# PR9023.net
KiCad netlist of a schematic drawn in EAGLE
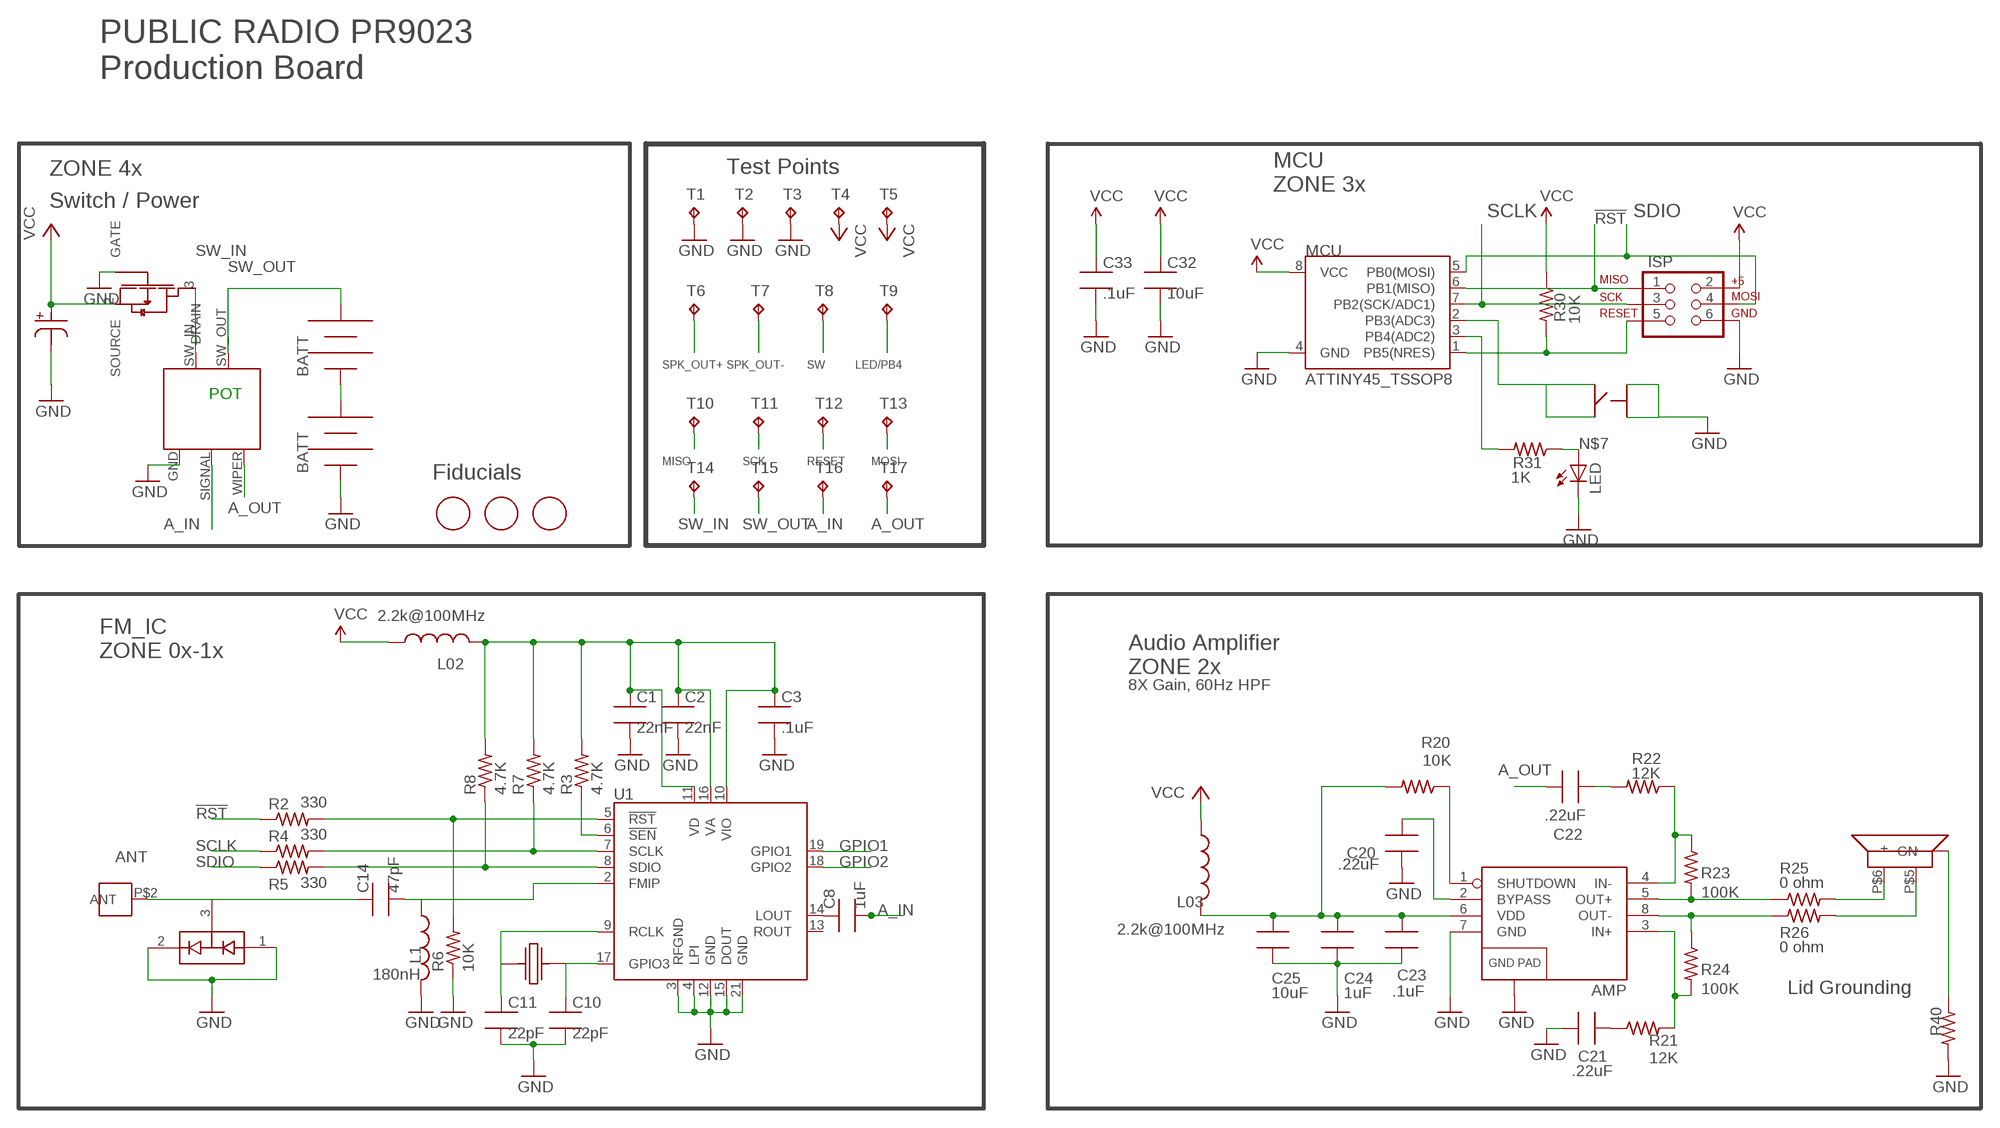
[diagram p0: schematic, sheet 1]

(export (version "E")
  (design (tool "Eeschema 10.0.6"))
  (components
    (comp (ref "AMP")
      (value "TPA6203A1")
      (footprint "eagle-import:8-MSOP")
      (libsource (lib "eagle-import") (part "TPA6203A1"))
    )
    (comp (ref "ANT_MOUNT")
      (value "DNP")
      (footprint "eagle-import:PEM_M3")
      (libsource (lib "eagle-import") (part "M3_PEMNUT"))
    )
    (comp (ref "C1")
      (value "22nF")
      (footprint "eagle-import:0603_CPL")
      (fields
        (field (name "MFG_PN") "CL10B223KB8NNNC")
        (field (name "TOL") "10%")
        (field (name "VOLTAGE") "16V")
      )
      (libsource (lib "eagle-import") (part "C_SMT_0603_CPL"))
    )
    (comp (ref "C2")
      (value "22nF")
      (footprint "eagle-import:0603_CPL")
      (fields
        (field (name "MFG_PN") "CL10B223KB8NNNC")
        (field (name "TOL") "10%")
        (field (name "VOLTAGE") "16V")
      )
      (libsource (lib "eagle-import") (part "C_SMT_0603_CPL"))
    )
    (comp (ref "C3")
      (value ".1uF")
      (footprint "eagle-import:0603_CPL")
      (fields
        (field (name "MFG_PN") "CL10B104KB8SFNC")
        (field (name "TOL") "10%")
        (field (name "VOLTAGE") "16V")
      )
      (libsource (lib "eagle-import") (part "C_SMT_0603_CPL"))
    )
    (comp (ref "C8")
      (value "1uF")
      (footprint "eagle-import:0603_CPL")
      (fields
        (field (name "MFG_PN") "CL10B105KP8NNNC")
        (field (name "TOL") "10%")
        (field (name "VOLTAGE") "10V")
      )
      (libsource (lib "eagle-import") (part "C_SMT_0603_CPL"))
    )
    (comp (ref "C10")
      (value "22pF")
      (footprint "eagle-import:0603_CPL")
      (fields
        (field (name "MFG_PN") "C1608C0G1H220J080AA")
        (field (name "TOL") "5%")
        (field (name "VOLTAGE") "50V")
      )
      (libsource (lib "eagle-import") (part "C_SMT_0603_CPL"))
    )
    (comp (ref "C11")
      (value "22pF")
      (footprint "eagle-import:0603_CPL")
      (fields
        (field (name "MFG_PN") "C1608C0G1H220J080AA")
        (field (name "TOL") "5%")
        (field (name "VOLTAGE") "50V")
      )
      (libsource (lib "eagle-import") (part "C_SMT_0603_CPL"))
    )
    (comp (ref "C14")
      (value "47pF")
      (footprint "eagle-import:0603_CPL")
      (fields
        (field (name "MFG_PN") "CL10C470JB8NCNC")
        (field (name "TOL") "5%")
        (field (name "VOLTAGE") "50V")
      )
      (libsource (lib "eagle-import") (part "C_SMT_0603_CPL"))
    )
    (comp (ref "C20")
      (value ".22uF")
      (footprint "eagle-import:0603_CPL")
      (fields
        (field (name "MFG_PN") "C1608X7R1C224K080AC")
        (field (name "TOL") "10%")
        (field (name "VOLTAGE") "16V")
      )
      (libsource (lib "eagle-import") (part "C_SMT_0603_CPL"))
    )
    (comp (ref "C21")
      (value ".22uF")
      (footprint "eagle-import:0603_CPL")
      (fields
        (field (name "MFG_PN") "C1608X7R1C224K080AC")
        (field (name "TOL") "10%")
        (field (name "VOLTAGE") "16V")
      )
      (libsource (lib "eagle-import") (part "C_SMT_0603_CPL"))
    )
    (comp (ref "C22")
      (value ".22uF")
      (footprint "eagle-import:0603_CPL")
      (fields
        (field (name "MFG_PN") "C1608X7R1C224K080AC")
        (field (name "TOL") "10%")
        (field (name "VOLTAGE") "16V")
      )
      (libsource (lib "eagle-import") (part "C_SMT_0603_CPL"))
    )
    (comp (ref "C23")
      (value ".1uF")
      (footprint "eagle-import:0603_CPL")
      (fields
        (field (name "MFG_PN") "CL10B104KB8SFNC")
        (field (name "TOL") "10%")
        (field (name "VOLTAGE") "16V")
      )
      (libsource (lib "eagle-import") (part "C_SMT_0603_CPL"))
    )
    (comp (ref "C24")
      (value "1uF")
      (footprint "eagle-import:0603_CPL")
      (fields
        (field (name "MFG_PN") "CL10B105KP8NNNC")
        (field (name "TOL") "10%")
        (field (name "VOLTAGE") "10V")
      )
      (libsource (lib "eagle-import") (part "C_SMT_0603_CPL"))
    )
    (comp (ref "C25")
      (value "10uF")
      (footprint "eagle-import:0603_CPL")
      (fields
        (field (name "MFG_PN") "CL10A106MQ8NNNC")
        (field (name "TOL") "20%")
        (field (name "VOLTAGE") "6.3V")
      )
      (libsource (lib "eagle-import") (part "C_SMT_0603_CPL"))
    )
    (comp (ref "C32")
      (value "10uF")
      (footprint "eagle-import:0603_CPL")
      (fields
        (field (name "MFG_PN") "CL10A106MQ8NNNC")
        (field (name "TOL") "20%")
        (field (name "VOLTAGE") "6.3V")
      )
      (libsource (lib "eagle-import") (part "C_SMT_0603_CPL"))
    )
    (comp (ref "C33")
      (value ".1uF")
      (footprint "eagle-import:0603_CPL")
      (fields
        (field (name "MFG_PN") "CL10B104KB8SFNC")
        (field (name "TOL") "10%")
        (field (name "VOLTAGE") "16V")
      )
      (libsource (lib "eagle-import") (part "C_SMT_0603_CPL"))
    )
    (comp (ref "C40")
      (value "220uF")
      (footprint "eagle-import:NICHICON_UD_63")
      (fields (field (name "TOL") "20%") (field (name "VOLTAGE") "16V"))
      (libsource (lib "eagle-import") (part "NICHICON_SERIESUD"))
    )
    (comp (ref "D1")
      (value "BAV99")
      (footprint "eagle-import:SOT23_CPL")
      (fields (field (name "MFG_PN") "BAV99,215"))
      (libsource (lib "eagle-import") (part "BAV99"))
    )
    (comp (ref "FET1")
      (value "AO3435")
      (footprint "eagle-import:SOT23_CPL")
      (fields (field (name "MFG_PN") "AO3435"))
      (libsource (lib "eagle-import") (part "AO3435"))
    )
    (comp (ref "ISP")
      (value "AVR_SPI_PRG_6NS")
      (footprint "eagle-import:2X3-NS")
      (libsource (lib "eagle-import") (part "AVR_SPI_PRG_6NS"))
    )
    (comp (ref "JP5")
      (value "BK-92_MPD_AA_BATT_CLIP")
      (footprint "eagle-import:BK92_AA_BATT")
      (fields (field (name "MFG_PN") "2 of BK92 - supplied by CL Labs"))
      (libsource (lib "eagle-import") (part "BK-92_MPD_AA_BATT_CLIP"))
    )
    (comp (ref "JP6")
      (value "BK-92_MPD_AA_BATT_CLIP")
      (footprint "eagle-import:BK92_AA_BATT")
      (fields (field (name "MFG_PN") "2 of BK92 - supplied by CL Labs"))
      (libsource (lib "eagle-import") (part "BK-92_MPD_AA_BATT_CLIP"))
    )
    (comp (ref "L1")
      (value "180nH")
      (footprint "eagle-import:0805_ADAFRUIT")
      (fields
        (field (name "CURRENT") "400mA")
        (field (name "DCR") "640m")
        (field (name "MFG_PN") "AISC-0805-R18J-T")
        (field (name "TOL") "5%")
      )
      (libsource (lib "eagle-import") (part "L_SMT_0805_ADAFRUIT"))
    )
    (comp (ref "L02")
      (value "2.2k@100MHz")
      (footprint "eagle-import:0603_CPL")
      (fields
        (field (name "CURRENT") "150mA")
        (field (name "DCR") "2.3")
        (field (name "MFG_PN") "HZ0603A222R-10")
      )
      (libsource (lib "eagle-import") (part "L_SMT_0603_CPL"))
    )
    (comp (ref "L03")
      (value "2.2k@100MHz")
      (footprint "eagle-import:0603_CPL")
      (fields
        (field (name "CURRENT") "150mA")
        (field (name "DCR") "2.3")
        (field (name "MFG_PN") "HZ0603A222R-10")
      )
      (libsource (lib "eagle-import") (part "L_SMT_0603_CPL"))
    )
    (comp (ref "LED")
      (value "LEDCHIPLED_0805")
      (footprint "eagle-import:CHIPLED_0805")
      (libsource (lib "eagle-import") (part "LEDCHIPLED_0805"))
    )
    (comp (ref "MARK1")
      (value "FIDUCIAL")
      (footprint "eagle-import:FIDUCIAL_1MM")
      (libsource (lib "eagle-import") (part "FIDUCIAL"))
    )
    (comp (ref "MARK2")
      (value "FIDUCIAL")
      (footprint "eagle-import:FIDUCIAL_1MM")
      (libsource (lib "eagle-import") (part "FIDUCIAL"))
    )
    (comp (ref "MARK3")
      (value "FIDUCIAL")
      (footprint "eagle-import:FIDUCIAL_1MM")
      (libsource (lib "eagle-import") (part "FIDUCIAL"))
    )
    (comp (ref "MCU")
      (value "ATTINY45_TSSOP8")
      (footprint "eagle-import:TSSOP-8")
      (libsource (lib "eagle-import") (part "ATTINY45_TSSOP8"))
    )
    (comp (ref "R1")
      (value "RV170SF_TAIWANA_POT_SW")
      (footprint "eagle-import:RV170SF_SW_POT")
      (fields (field (name "MFG_PN") "RV170SF-43-20F-A10K - supplied by CL Labs"))
      (libsource (lib "eagle-import") (part "RV170SF_TAIWANA_POT_SW"))
    )
    (comp (ref "R2")
      (value "330")
      (footprint "eagle-import:0603_CPL")
      (fields (field (name "MFG_PN") "MCR03ERTJ331") (field (name "POWER") "1/10W") (field (name "TOL") "5%"))
      (libsource (lib "eagle-import") (part "R_SMT_R0603_CPL"))
    )
    (comp (ref "R3")
      (value "4.7K")
      (footprint "eagle-import:0603_CPL")
      (fields
        (field (name "MFG_PN") "ERJ-3EKF4701V")
        (field (name "POWER") "1/10W")
        (field (name "TOL") "1%")
      )
      (libsource (lib "eagle-import") (part "R_SMT_R0603_CPL"))
    )
    (comp (ref "R4")
      (value "330")
      (footprint "eagle-import:0603_CPL")
      (fields (field (name "MFG_PN") "MCR03ERTJ331") (field (name "POWER") "1/10W") (field (name "TOL") "5%"))
      (libsource (lib "eagle-import") (part "R_SMT_R0603_CPL"))
    )
    (comp (ref "R5")
      (value "330")
      (footprint "eagle-import:0603_CPL")
      (fields (field (name "MFG_PN") "MCR03ERTJ331") (field (name "POWER") "1/10W") (field (name "TOL") "5%"))
      (libsource (lib "eagle-import") (part "R_SMT_R0603_CPL"))
    )
    (comp (ref "R6")
      (value "10K")
      (footprint "eagle-import:0603_CPL")
      (fields
        (field (name "MFG_PN") "ERJ-3GEYJ103V")
        (field (name "POWER") "1/10W")
        (field (name "TOL") "5%")
      )
      (libsource (lib "eagle-import") (part "R_SMT_R0603_CPL"))
    )
    (comp (ref "R7")
      (value "4.7K")
      (footprint "eagle-import:0603_CPL")
      (fields
        (field (name "MFG_PN") "ERJ-3EKF4701V")
        (field (name "POWER") "1/10W")
        (field (name "TOL") "1%")
      )
      (libsource (lib "eagle-import") (part "R_SMT_R0603_CPL"))
    )
    (comp (ref "R8")
      (value "4.7K")
      (footprint "eagle-import:0603_CPL")
      (fields
        (field (name "MFG_PN") "ERJ-3EKF4701V")
        (field (name "POWER") "1/10W")
        (field (name "TOL") "1%")
      )
      (libsource (lib "eagle-import") (part "R_SMT_R0603_CPL"))
    )
    (comp (ref "R20")
      (value "10K")
      (footprint "eagle-import:0603_CPL")
      (fields
        (field (name "MFG_PN") "ERJ-3GEYJ103V")
        (field (name "POWER") "1/10W")
        (field (name "TOL") "5%")
      )
      (libsource (lib "eagle-import") (part "R_SMT_R0603_CPL"))
    )
    (comp (ref "R21")
      (value "12K")
      (footprint "eagle-import:0603_CPL")
      (fields
        (field (name "MFG_PN") "RC0603FR-0712KL")
        (field (name "POWER") "1/10W")
        (field (name "TOL") "1%")
      )
      (libsource (lib "eagle-import") (part "R_SMT_R0603_CPL"))
    )
    (comp (ref "R22")
      (value "12K")
      (footprint "eagle-import:0603_CPL")
      (fields
        (field (name "MFG_PN") "RC0603FR-0712KL")
        (field (name "POWER") "1/10W")
        (field (name "TOL") "1%")
      )
      (libsource (lib "eagle-import") (part "R_SMT_R0603_CPL"))
    )
    (comp (ref "R23")
      (value "100K")
      (footprint "eagle-import:0603_CPL")
      (fields
        (field (name "MFG_PN") "ERJ-3EKF1003V")
        (field (name "POWER") "1/10W")
        (field (name "TOL") "1%")
      )
      (libsource (lib "eagle-import") (part "R_SMT_R0603_CPL"))
    )
    (comp (ref "R24")
      (value "100K")
      (footprint "eagle-import:0603_CPL")
      (fields
        (field (name "MFG_PN") "ERJ-3EKF1003V")
        (field (name "POWER") "1/10W")
        (field (name "TOL") "1%")
      )
      (libsource (lib "eagle-import") (part "R_SMT_R0603_CPL"))
    )
    (comp (ref "R25")
      (value "0 ohm")
      (footprint "eagle-import:0805_ADAFRUIT")
      (fields (field (name "MFG_PN") "ERJ-6GEY0R00V "))
      (libsource (lib "eagle-import") (part "R_SMT_0805_ADAFRUIT"))
    )
    (comp (ref "R26")
      (value "0 ohm")
      (footprint "eagle-import:0805_ADAFRUIT")
      (fields (field (name "MFG_PN") "ERJ-6GEY0R00V "))
      (libsource (lib "eagle-import") (part "R_SMT_0805_ADAFRUIT"))
    )
    (comp (ref "R30")
      (value "10K")
      (footprint "eagle-import:0603_CPL")
      (fields
        (field (name "MFG_PN") "ERJ-3GEYJ103V")
        (field (name "POWER") "1/10W")
        (field (name "TOL") "5%")
      )
      (libsource (lib "eagle-import") (part "R_SMT_R0603_CPL"))
    )
    (comp (ref "R31")
      (value "1K")
      (footprint "eagle-import:0603_CPL")
      (fields
        (field (name "MFG_PN") "ERJ-3EKF1001V")
        (field (name "POWER") "1/10W")
        (field (name "TOL") "1%")
      )
      (libsource (lib "eagle-import") (part "R_SMT_R0603_CPL"))
    )
    (comp (ref "R40")
      (value "DNP")
      (footprint "eagle-import:0603_CPL")
      (fields (field (name "MFG_PN") "ERJ-3GEY0R00V"))
      (libsource (lib "eagle-import") (part "R_SMT_R0603_CPL"))
    )
    (comp (ref "SPKR_PLACE")
      (value "DNP")
      (footprint "eagle-import:PR2024_SPKR_PLACE(SMD)")
      (libsource (lib "eagle-import") (part "PR2024_SPKR_SMD"))
    )
    (comp (ref "SW1")
      (value "ESWT_TL3315")
      (footprint "eagle-import:E_SWITCH_TL3315")
      (libsource (lib "eagle-import") (part "ESWT_TL3315"))
    )
    (comp (ref "T1")
      (value "TPTP20R")
      (footprint "eagle-import:TP20R")
      (libsource (lib "eagle-import") (part "TPTP20R"))
    )
    (comp (ref "T2")
      (value "TPTP20R")
      (footprint "eagle-import:TP20R")
      (libsource (lib "eagle-import") (part "TPTP20R"))
    )
    (comp (ref "T3")
      (value "TPTP20R")
      (footprint "eagle-import:TP20R")
      (libsource (lib "eagle-import") (part "TPTP20R"))
    )
    (comp (ref "T4")
      (value "TPTP20R")
      (footprint "eagle-import:TP20R")
      (libsource (lib "eagle-import") (part "TPTP20R"))
    )
    (comp (ref "T5")
      (value "TPTP20R")
      (footprint "eagle-import:TP20R")
      (libsource (lib "eagle-import") (part "TPTP20R"))
    )
    (comp (ref "T6")
      (value "TPTP20R")
      (footprint "eagle-import:TP20R")
      (libsource (lib "eagle-import") (part "TPTP20R"))
    )
    (comp (ref "T7")
      (value "TPTP20R")
      (footprint "eagle-import:TP20R")
      (libsource (lib "eagle-import") (part "TPTP20R"))
    )
    (comp (ref "T8")
      (value "TPTP20R")
      (footprint "eagle-import:TP20R")
      (libsource (lib "eagle-import") (part "TPTP20R"))
    )
    (comp (ref "T9")
      (value "TPTP20R")
      (footprint "eagle-import:TP20R")
      (libsource (lib "eagle-import") (part "TPTP20R"))
    )
    (comp (ref "T10")
      (value "TPTP20R")
      (footprint "eagle-import:TP20R")
      (libsource (lib "eagle-import") (part "TPTP20R"))
    )
    (comp (ref "T11")
      (value "TPTP20R")
      (footprint "eagle-import:TP20R")
      (libsource (lib "eagle-import") (part "TPTP20R"))
    )
    (comp (ref "T12")
      (value "TPTP20R")
      (footprint "eagle-import:TP20R")
      (libsource (lib "eagle-import") (part "TPTP20R"))
    )
    (comp (ref "T13")
      (value "TPTP20R")
      (footprint "eagle-import:TP20R")
      (libsource (lib "eagle-import") (part "TPTP20R"))
    )
    (comp (ref "T14")
      (value "TPTP20R")
      (footprint "eagle-import:TP20R")
      (libsource (lib "eagle-import") (part "TPTP20R"))
    )
    (comp (ref "T15")
      (value "TPTP20R")
      (footprint "eagle-import:TP20R")
      (libsource (lib "eagle-import") (part "TPTP20R"))
    )
    (comp (ref "T16")
      (value "TPTP20R")
      (footprint "eagle-import:TP20R")
      (libsource (lib "eagle-import") (part "TPTP20R"))
    )
    (comp (ref "T17")
      (value "TPTP20R")
      (footprint "eagle-import:TP20R")
      (libsource (lib "eagle-import") (part "TPTP20R"))
    )
    (comp (ref "U1")
      (value "SI4702-C19-GMR")
      (footprint "eagle-import:SI470X_20_QFN")
      (fields (field (name "MFG_PN") "Si4702 C19 GM - supplied by CL Labs"))
      (libsource (lib "eagle-import") (part "SI4702-C19-GMR"))
    )
    (comp (ref "X1")
      (value "ABS25XTAL")
      (footprint "eagle-import:4-SOJ")
      (libsource (lib "eagle-import") (part "ABS25XTAL"))
    )
  )
  (nets
    (net (code "1") (name "/ANT") (class "Default")
      (node (ref "ANT_MOUNT") (pin "P$2") (pinfunction "ANT_P$2") (pintype "bidirectional"))
      (node (ref "C14") (pin "1") (pinfunction "1_1") (pintype "passive"))
      (node (ref "D1") (pin "3") (pinfunction "COM_3") (pintype "bidirectional"))
    )
    (net (code "2") (name "/A_IN") (class "Default")
      (node (ref "C8") (pin "2") (pinfunction "2_2") (pintype "passive"))
      (node (ref "R1") (pin "SIGNAL") (pinfunction "SIGNAL_SIGNAL") (pintype "bidirectional"))
      (node (ref "T16") (pin "TP") (pinfunction "TP_TP") (pintype "input"))
    )
    (net (code "3") (name "/A_OUT") (class "Default")
      (node (ref "C22") (pin "2") (pinfunction "2_2") (pintype "passive"))
      (node (ref "R1") (pin "WIPER") (pinfunction "WIPER_WIPER") (pintype "bidirectional"))
      (node (ref "T17") (pin "TP") (pinfunction "TP_TP") (pintype "input"))
    )
    (net (code "4") (name "/GPIO1") (class "Default")
      (node (ref "U1") (pin "19") (pinfunction "GPIO1_19") (pintype "bidirectional"))
    )
    (net (code "5") (name "/GPIO2") (class "Default")
      (node (ref "U1") (pin "18") (pinfunction "GPIO2_18") (pintype "bidirectional"))
    )
    (net (code "6") (name "/LED{slash}PB4") (class "Default")
      (node (ref "MCU") (pin "3") (pinfunction "PB4(ADC2)_3") (pintype "bidirectional"))
      (node (ref "R31") (pin "2") (pinfunction "2_2") (pintype "passive"))
      (node (ref "T9") (pin "TP") (pinfunction "TP_TP") (pintype "input"))
    )
    (net (code "7") (name "/N$7") (class "Default")
      (node (ref "LED") (pin "A") (pinfunction "A_A") (pintype "passive"))
      (node (ref "R31") (pin "1") (pinfunction "1_1") (pintype "passive"))
    )
    (net (code "8") (name "/RESET") (class "Default")
      (node (ref "ISP") (pin "5") (pinfunction "5_5") (pintype "passive"))
      (node (ref "MCU") (pin "1") (pinfunction "PB5(NRES)_1") (pintype "bidirectional"))
      (node (ref "R30") (pin "2") (pinfunction "2_2") (pintype "passive"))
      (node (ref "T12") (pin "TP") (pinfunction "TP_TP") (pintype "input"))
    )
    (net (code "9") (name "/SCLK") (class "Default")
      (node (ref "ISP") (pin "3") (pinfunction "3_3") (pintype "passive"))
      (node (ref "MCU") (pin "7") (pinfunction "PB2(SCK/ADC1)_7") (pintype "bidirectional"))
      (node (ref "R4") (pin "1") (pinfunction "1_1") (pintype "passive"))
      (node (ref "T11") (pin "TP") (pinfunction "TP_TP") (pintype "input"))
    )
    (net (code "10") (name "/SDIO") (class "Default")
      (node (ref "ISP") (pin "4") (pinfunction "4_4") (pintype "passive"))
      (node (ref "MCU") (pin "5") (pinfunction "PB0(MOSI)_5") (pintype "bidirectional"))
      (node (ref "R5") (pin "1") (pinfunction "1_1") (pintype "passive"))
      (node (ref "T13") (pin "TP") (pinfunction "TP_TP") (pintype "input"))
    )
    (net (code "11") (name "/SPK_OUT+") (class "Default")
      (node (ref "R25") (pin "2") (pinfunction "2_2") (pintype "passive"))
      (node (ref "SPKR_PLACE") (pin "P$6") (pinfunction "+_P$6") (pintype "bidirectional"))
      (node (ref "T6") (pin "TP") (pinfunction "TP_TP") (pintype "input"))
    )
    (net (code "12") (name "/SPK_OUT-") (class "Default")
      (node (ref "R26") (pin "2") (pinfunction "2_2") (pintype "passive"))
      (node (ref "SPKR_PLACE") (pin "P$5") (pinfunction "-_P$5") (pintype "bidirectional"))
      (node (ref "T7") (pin "TP") (pinfunction "TP_TP") (pintype "input"))
    )
    (net (code "13") (name "/SW") (class "Default")
      (node (ref "MCU") (pin "2") (pinfunction "PB3(ADC3)_2") (pintype "bidirectional"))
      (node (ref "SW1") (pin "P$3") (pinfunction "P$3_P$3") (pintype "bidirectional"))
      (node (ref "SW1") (pin "P$4") (pinfunction "P$4_P$4") (pintype "bidirectional"))
      (node (ref "T8") (pin "TP") (pinfunction "TP_TP") (pintype "input"))
    )
    (net (code "14") (name "/SW_IN") (class "Default")
      (node (ref "FET1") (pin "3") (pinfunction "DRAIN_3") (pintype "bidirectional"))
      (node (ref "R1") (pin "SW_IN") (pinfunction "SW_IN_SW_IN") (pintype "bidirectional"))
      (node (ref "T14") (pin "TP") (pinfunction "TP_TP") (pintype "input"))
    )
    (net (code "15") (name "/SW_OUT") (class "Default")
      (node (ref "JP5") (pin "POS") (pinfunction "POS_POS") (pintype "bidirectional"))
      (node (ref "JP5") (pin "POS@2") (pinfunction "POS_POS@2") (pintype "bidirectional"))
      (node (ref "R1") (pin "SW_OUT") (pinfunction "SW_OUT_SW_OUT") (pintype "bidirectional"))
      (node (ref "T15") (pin "TP") (pinfunction "TP_TP") (pintype "input"))
    )
    (net (code "16") (name "/~{RST}") (class "Default")
      (node (ref "ISP") (pin "1") (pinfunction "1_1") (pintype "passive"))
      (node (ref "MCU") (pin "6") (pinfunction "PB1(MISO)_6") (pintype "bidirectional"))
      (node (ref "R2") (pin "1") (pinfunction "1_1") (pintype "passive"))
      (node (ref "T10") (pin "TP") (pinfunction "TP_TP") (pintype "input"))
    )
    (net (code "17") (name "GND") (class "Default")
      (node (ref "AMP") (pin "7") (pinfunction "GND_7") (pintype "power_in"))
      (node (ref "AMP") (pin "9") (pinfunction "GND_9") (pintype "power_in"))
      (node (ref "C1") (pin "2") (pinfunction "2_2") (pintype "passive"))
      (node (ref "C10") (pin "2") (pinfunction "2_2") (pintype "passive"))
      (node (ref "C11") (pin "2") (pinfunction "2_2") (pintype "passive"))
      (node (ref "C2") (pin "2") (pinfunction "2_2") (pintype "passive"))
      (node (ref "C20") (pin "1") (pinfunction "1_1") (pintype "passive"))
      (node (ref "C21") (pin "1") (pinfunction "1_1") (pintype "passive"))
      (node (ref "C23") (pin "2") (pinfunction "2_2") (pintype "passive"))
      (node (ref "C24") (pin "2") (pinfunction "2_2") (pintype "passive"))
      (node (ref "C25") (pin "2") (pinfunction "2_2") (pintype "passive"))
      (node (ref "C3") (pin "2") (pinfunction "2_2") (pintype "passive"))
      (node (ref "C32") (pin "2") (pinfunction "2_2") (pintype "passive"))
      (node (ref "C33") (pin "2") (pinfunction "2_2") (pintype "passive"))
      (node (ref "C40") (pin "P$2") (pinfunction "P$2_P$2") (pintype "bidirectional"))
      (node (ref "D1") (pin "1") (pinfunction "A1_1") (pintype "bidirectional"))
      (node (ref "D1") (pin "2") (pinfunction "C2_2") (pintype "bidirectional"))
      (node (ref "FET1") (pin "1") (pinfunction "GATE_1") (pintype "bidirectional"))
      (node (ref "ISP") (pin "6") (pinfunction "6_6") (pintype "passive"))
      (node (ref "JP6") (pin "NEG") (pinfunction "NEG_NEG") (pintype "bidirectional"))
      (node (ref "JP6") (pin "NEG@2") (pinfunction "NEG_NEG@2") (pintype "bidirectional"))
      (node (ref "L1") (pin "2") (pinfunction "2_2") (pintype "passive"))
      (node (ref "LED") (pin "C") (pinfunction "C_C") (pintype "passive"))
      (node (ref "MCU") (pin "4") (pinfunction "GND_4") (pintype "bidirectional"))
      (node (ref "R1") (pin "GND") (pinfunction "GND_GND") (pintype "bidirectional"))
      (node (ref "R40") (pin "2") (pinfunction "2_2") (pintype "passive"))
      (node (ref "R6") (pin "1") (pinfunction "1_1") (pintype "passive"))
      (node (ref "SW1") (pin "P$1") (pinfunction "P$1_P$1") (pintype "bidirectional"))
      (node (ref "SW1") (pin "P$2") (pinfunction "P$2_P$2") (pintype "bidirectional"))
      (node (ref "T1") (pin "TP") (pinfunction "TP_TP") (pintype "input"))
      (node (ref "T2") (pin "TP") (pinfunction "TP_TP") (pintype "input"))
      (node (ref "T3") (pin "TP") (pinfunction "TP_TP") (pintype "input"))
      (node (ref "U1") (pin "12") (pinfunction "GND_12") (pintype "bidirectional"))
      (node (ref "U1") (pin "15") (pinfunction "DOUT_15") (pintype "bidirectional"))
      (node (ref "U1") (pin "21") (pinfunction "GND_21") (pintype "bidirectional"))
      (node (ref "U1") (pin "3") (pinfunction "RFGND_3") (pintype "bidirectional"))
      (node (ref "U1") (pin "4") (pinfunction "LPI_4") (pintype "bidirectional"))
    )
    (net (code "18") (name "Net-(AMP-BYPASS)") (class "Default")
      (node (ref "AMP") (pin "2") (pinfunction "BYPASS_2") (pintype "bidirectional"))
      (node (ref "C20") (pin "2") (pinfunction "2_2") (pintype "passive"))
    )
    (net (code "19") (name "Net-(AMP-IN+)") (class "Default")
      (node (ref "AMP") (pin "3") (pinfunction "IN+_3") (pintype "bidirectional"))
      (node (ref "R21") (pin "2") (pinfunction "2_2") (pintype "passive"))
      (node (ref "R24") (pin "2") (pinfunction "2_2") (pintype "passive"))
    )
    (net (code "20") (name "Net-(AMP-IN-)") (class "Default")
      (node (ref "AMP") (pin "4") (pinfunction "IN-_4") (pintype "bidirectional"))
      (node (ref "R22") (pin "1") (pinfunction "1_1") (pintype "passive"))
      (node (ref "R23") (pin "1") (pinfunction "1_1") (pintype "passive"))
    )
    (net (code "21") (name "Net-(AMP-OUT+)") (class "Default")
      (node (ref "AMP") (pin "5") (pinfunction "OUT+_5") (pintype "bidirectional"))
      (node (ref "R23") (pin "2") (pinfunction "2_2") (pintype "passive"))
      (node (ref "R25") (pin "1") (pinfunction "1_1") (pintype "passive"))
    )
    (net (code "22") (name "Net-(AMP-OUT-)") (class "Default")
      (node (ref "AMP") (pin "8") (pinfunction "OUT-_8") (pintype "bidirectional"))
      (node (ref "R24") (pin "1") (pinfunction "1_1") (pintype "passive"))
      (node (ref "R26") (pin "1") (pinfunction "1_1") (pintype "passive"))
    )
    (net (code "23") (name "Net-(AMP-SHUTDOWN)") (class "Default")
      (node (ref "AMP") (pin "1") (pinfunction "SHUTDOWN_1") (pintype "input"))
      (node (ref "R20") (pin "1") (pinfunction "1_1") (pintype "passive"))
    )
    (net (code "24") (name "Net-(AMP-VDD)") (class "Default")
      (node (ref "AMP") (pin "6") (pinfunction "VDD_6") (pintype "power_in"))
      (node (ref "C23") (pin "1") (pinfunction "1_1") (pintype "passive"))
      (node (ref "C24") (pin "1") (pinfunction "1_1") (pintype "passive"))
      (node (ref "C25") (pin "1") (pinfunction "1_1") (pintype "passive"))
      (node (ref "L03") (pin "2") (pinfunction "2_2") (pintype "passive"))
      (node (ref "R20") (pin "2") (pinfunction "2_2") (pintype "passive"))
    )
    (net (code "25") (name "Net-(C21-Pad2)") (class "Default")
      (node (ref "C21") (pin "2") (pinfunction "2_2") (pintype "passive"))
      (node (ref "R21") (pin "1") (pinfunction "1_1") (pintype "passive"))
    )
    (net (code "26") (name "Net-(C22-Pad1)") (class "Default")
      (node (ref "C22") (pin "1") (pinfunction "1_1") (pintype "passive"))
      (node (ref "R22") (pin "2") (pinfunction "2_2") (pintype "passive"))
    )
    (net (code "27") (name "Net-(JP5-NEG-PadNEG@2)") (class "Default")
      (node (ref "JP5") (pin "NEG") (pinfunction "NEG_NEG") (pintype "bidirectional"))
      (node (ref "JP5") (pin "NEG@2") (pinfunction "NEG_NEG@2") (pintype "bidirectional"))
      (node (ref "JP6") (pin "POS") (pinfunction "POS_POS") (pintype "bidirectional"))
      (node (ref "JP6") (pin "POS@2") (pinfunction "POS_POS@2") (pintype "bidirectional"))
    )
    (net (code "28") (name "Net-(SPKR_PLACE-GN)") (class "Default")
      (node (ref "R40") (pin "1") (pinfunction "1_1") (pintype "passive"))
      (node (ref "SPKR_PLACE") (pin "P$4") (pinfunction "GN_P$4") (pintype "bidirectional"))
    )
    (net (code "29") (name "Net-(U1-FMIP)") (class "Default")
      (node (ref "C14") (pin "2") (pinfunction "2_2") (pintype "passive"))
      (node (ref "L1") (pin "1") (pinfunction "1_1") (pintype "passive"))
      (node (ref "U1") (pin "2") (pinfunction "FMIP_2") (pintype "bidirectional"))
    )
    (net (code "30") (name "Net-(U1-GPIO3)") (class "Default")
      (node (ref "C10") (pin "1") (pinfunction "1_1") (pintype "passive"))
      (node (ref "U1") (pin "17") (pinfunction "GPIO3_17") (pintype "bidirectional"))
      (node (ref "X1") (pin "P$4") (pinfunction "P$4_P$4") (pintype "bidirectional"))
    )
    (net (code "31") (name "Net-(U1-LOUT)") (class "Default")
      (node (ref "C8") (pin "1") (pinfunction "1_1") (pintype "passive"))
      (node (ref "U1") (pin "14") (pinfunction "LOUT_14") (pintype "bidirectional"))
    )
    (net (code "32") (name "Net-(U1-RCLK)") (class "Default")
      (node (ref "C11") (pin "1") (pinfunction "1_1") (pintype "passive"))
      (node (ref "U1") (pin "9") (pinfunction "RCLK_9") (pintype "bidirectional"))
      (node (ref "X1") (pin "P$1") (pinfunction "P$1_P$1") (pintype "bidirectional"))
    )
    (net (code "33") (name "Net-(U1-SCLK)") (class "Default")
      (node (ref "R4") (pin "2") (pinfunction "2_2") (pintype "passive"))
      (node (ref "R7") (pin "1") (pinfunction "1_1") (pintype "passive"))
      (node (ref "U1") (pin "7") (pinfunction "SCLK_7") (pintype "bidirectional"))
    )
    (net (code "34") (name "Net-(U1-SDIO)") (class "Default")
      (node (ref "R5") (pin "2") (pinfunction "2_2") (pintype "passive"))
      (node (ref "R8") (pin "1") (pinfunction "1_1") (pintype "passive"))
      (node (ref "U1") (pin "8") (pinfunction "SDIO_8") (pintype "bidirectional"))
    )
    (net (code "35") (name "Net-(U1-VA)") (class "Default")
      (node (ref "C1") (pin "1") (pinfunction "1_1") (pintype "passive"))
      (node (ref "C2") (pin "1") (pinfunction "1_1") (pintype "passive"))
      (node (ref "C3") (pin "1") (pinfunction "1_1") (pintype "passive"))
      (node (ref "L02") (pin "2") (pinfunction "2_2") (pintype "passive"))
      (node (ref "R3") (pin "2") (pinfunction "2_2") (pintype "passive"))
      (node (ref "R7") (pin "2") (pinfunction "2_2") (pintype "passive"))
      (node (ref "R8") (pin "2") (pinfunction "2_2") (pintype "passive"))
      (node (ref "U1") (pin "10") (pinfunction "VIO_10") (pintype "bidirectional"))
      (node (ref "U1") (pin "11") (pinfunction "VD_11") (pintype "bidirectional"))
      (node (ref "U1") (pin "16") (pinfunction "VA_16") (pintype "bidirectional"))
    )
    (net (code "36") (name "Net-(U1-~{RST})") (class "Default")
      (node (ref "R2") (pin "2") (pinfunction "2_2") (pintype "passive"))
      (node (ref "R6") (pin "2") (pinfunction "2_2") (pintype "passive"))
      (node (ref "U1") (pin "5") (pinfunction "~{RST}_5") (pintype "bidirectional"))
    )
    (net (code "37") (name "Net-(U1-~{SEN})") (class "Default")
      (node (ref "R3") (pin "1") (pinfunction "1_1") (pintype "passive"))
      (node (ref "U1") (pin "6") (pinfunction "~{SEN}_6") (pintype "bidirectional"))
    )
    (net (code "38") (name "VCC") (class "Default")
      (node (ref "C32") (pin "1") (pinfunction "1_1") (pintype "passive"))
      (node (ref "C33") (pin "1") (pinfunction "1_1") (pintype "passive"))
      (node (ref "C40") (pin "P$1") (pinfunction "P$1_P$1") (pintype "bidirectional"))
      (node (ref "FET1") (pin "2") (pinfunction "SOURCE_2") (pintype "bidirectional"))
      (node (ref "ISP") (pin "2") (pinfunction "2_2") (pintype "passive"))
      (node (ref "L02") (pin "1") (pinfunction "1_1") (pintype "passive"))
      (node (ref "L03") (pin "1") (pinfunction "1_1") (pintype "passive"))
      (node (ref "MCU") (pin "8") (pinfunction "VCC_8") (pintype "bidirectional"))
      (node (ref "R30") (pin "1") (pinfunction "1_1") (pintype "passive"))
      (node (ref "T4") (pin "TP") (pinfunction "TP_TP") (pintype "input"))
      (node (ref "T5") (pin "TP") (pinfunction "TP_TP") (pintype "input"))
    )
    (net (code "39") (name "unconnected-(U1-ROUT-Pad13)") (class "Default")
      (node (ref "U1") (pin "13") (pinfunction "ROUT_13") (pintype "bidirectional"))
    )
  )
)
